# Core_Shield_Shield.net
KiCad netlist of a schematic drawn in EAGLE
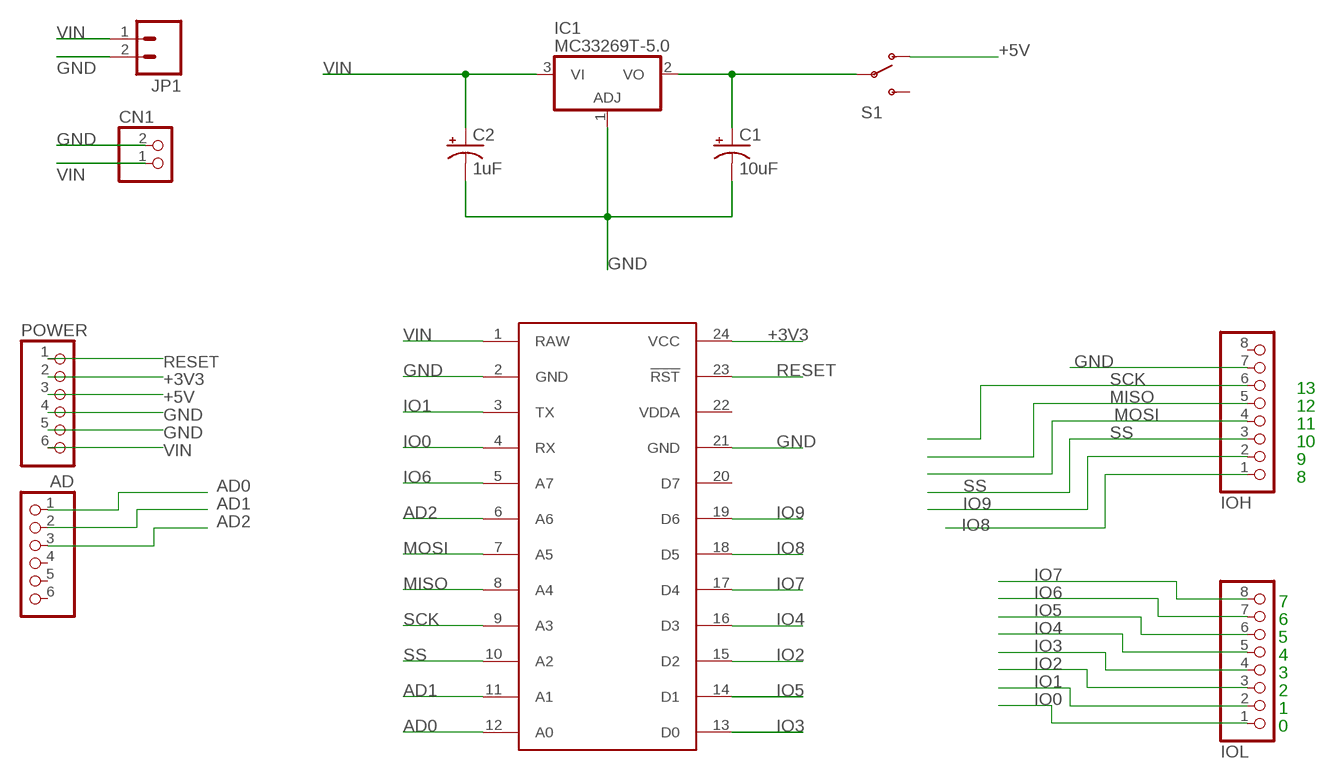
[diagram p0: schematic, sheet 1]

(export (version "E")
  (design (tool "Eeschema 10.0.6"))
  (components
    (comp (ref "AD")
      (value "PINHD-1X6")
      (footprint "eagle-import:1X06")
      (libsource (lib "eagle-import") (part "PINHD-1X6"))
    )
    (comp (ref "C1")
      (value "10uF")
      (footprint "eagle-import:CPOL-RADIAL-10UF-25V")
      (libsource (lib "eagle-import") (part "CAP_POLPTH2"))
    )
    (comp (ref "C2")
      (value "1uF")
      (footprint "eagle-import:CPOL-RADIAL-10UF-25V")
      (libsource (lib "eagle-import") (part "CAP_POLPTH2"))
    )
    (comp (ref "CN1")
      (value "JST_2PIN-THM")
      (footprint "eagle-import:JST-PH-2-THM")
      (libsource (lib "eagle-import") (part "JST_2PIN-THM"))
    )
    (comp (ref "IC1")
      (value "MC33269T-5.0")
      (footprint "eagle-import:TO220V")
      (libsource (lib "eagle-import") (part "MC33269?T-5.0"))
    )
    (comp (ref "IOH")
      (value "PINHD-1X8")
      (footprint "eagle-import:1X08")
      (libsource (lib "eagle-import") (part "PINHD-1X8"))
    )
    (comp (ref "IOL")
      (value "PINHD-1X8")
      (footprint "eagle-import:1X08")
      (libsource (lib "eagle-import") (part "PINHD-1X8"))
    )
    (comp (ref "JP1")
      (value "M02LOCK")
      (footprint "eagle-import:1X02_LOCK")
      (libsource (lib "eagle-import") (part "M02LOCK"))
    )
    (comp (ref "POWER")
      (value "PINHD-1X6")
      (footprint "eagle-import:1X06")
      (libsource (lib "eagle-import") (part "PINHD-1X6"))
    )
    (comp (ref "S1")
      (value "SWITCH-SPDTPTH")
      (footprint "eagle-import:SWITCH-SPDT")
      (libsource (lib "eagle-import") (part "SWITCH-SPDTPTH"))
    )
    (comp (ref "U$1")
      (value "SPARK_CORECORE")
      (footprint "eagle-import:SPARK_CORE")
      (libsource (lib "eagle-import") (part "SPARK_CORECORE"))
    )
  )
  (nets
    (net (code "1") (name "/+3V3") (class "Default")
      (node (ref "POWER") (pin "2") (pinfunction "2_2") (pintype "passive"))
      (node (ref "U$1") (pin "24") (pinfunction "VCC_24") (pintype "power_in"))
    )
    (net (code "2") (name "/+5V") (class "Default")
      (node (ref "POWER") (pin "3") (pinfunction "3_3") (pintype "passive"))
      (node (ref "S1") (pin "1") (pinfunction "O_1") (pintype "passive"))
    )
    (net (code "3") (name "/AD0") (class "Default")
      (node (ref "AD") (pin "1") (pinfunction "1_1") (pintype "passive"))
      (node (ref "U$1") (pin "12") (pinfunction "A0_12") (pintype "bidirectional"))
    )
    (net (code "4") (name "/AD1") (class "Default")
      (node (ref "AD") (pin "2") (pinfunction "2_2") (pintype "passive"))
      (node (ref "U$1") (pin "11") (pinfunction "A1_11") (pintype "bidirectional"))
    )
    (net (code "5") (name "/AD2") (class "Default")
      (node (ref "AD") (pin "3") (pinfunction "3_3") (pintype "passive"))
      (node (ref "U$1") (pin "6") (pinfunction "A6_6") (pintype "bidirectional"))
    )
    (net (code "6") (name "/GND") (class "Default")
      (node (ref "C1") (pin "2") (pinfunction "-_2") (pintype "passive"))
      (node (ref "C2") (pin "2") (pinfunction "-_2") (pintype "passive"))
      (node (ref "CN1") (pin "2") (pinfunction "1_2") (pintype "passive"))
      (node (ref "IC1") (pin "1") (pinfunction "ADJ_1") (pintype "input"))
      (node (ref "IOH") (pin "7") (pinfunction "7_7") (pintype "passive"))
      (node (ref "JP1") (pin "2") (pinfunction "2_2") (pintype "passive"))
      (node (ref "POWER") (pin "4") (pinfunction "4_4") (pintype "passive"))
      (node (ref "POWER") (pin "5") (pinfunction "5_5") (pintype "passive"))
      (node (ref "U$1") (pin "2") (pinfunction "GND_2") (pintype "power_in"))
      (node (ref "U$1") (pin "21") (pinfunction "GND_21") (pintype "power_in"))
    )
    (net (code "7") (name "/IO0") (class "Default")
      (node (ref "IOL") (pin "1") (pinfunction "1_1") (pintype "passive"))
      (node (ref "U$1") (pin "4") (pinfunction "RX_4") (pintype "bidirectional"))
    )
    (net (code "8") (name "/IO1") (class "Default")
      (node (ref "IOL") (pin "2") (pinfunction "2_2") (pintype "passive"))
      (node (ref "U$1") (pin "3") (pinfunction "TX_3") (pintype "bidirectional"))
    )
    (net (code "9") (name "/IO2") (class "Default")
      (node (ref "IOL") (pin "3") (pinfunction "3_3") (pintype "passive"))
      (node (ref "U$1") (pin "15") (pinfunction "D2_15") (pintype "bidirectional"))
    )
    (net (code "10") (name "/IO3") (class "Default")
      (node (ref "IOL") (pin "4") (pinfunction "4_4") (pintype "passive"))
      (node (ref "U$1") (pin "13") (pinfunction "D0_13") (pintype "bidirectional"))
    )
    (net (code "11") (name "/IO4") (class "Default")
      (node (ref "IOL") (pin "5") (pinfunction "5_5") (pintype "passive"))
      (node (ref "U$1") (pin "16") (pinfunction "D3_16") (pintype "bidirectional"))
    )
    (net (code "12") (name "/IO5") (class "Default")
      (node (ref "IOL") (pin "6") (pinfunction "6_6") (pintype "passive"))
      (node (ref "U$1") (pin "14") (pinfunction "D1_14") (pintype "bidirectional"))
    )
    (net (code "13") (name "/IO6") (class "Default")
      (node (ref "IOL") (pin "7") (pinfunction "7_7") (pintype "passive"))
      (node (ref "U$1") (pin "5") (pinfunction "A7_5") (pintype "bidirectional"))
    )
    (net (code "14") (name "/IO7") (class "Default")
      (node (ref "IOL") (pin "8") (pinfunction "8_8") (pintype "passive"))
      (node (ref "U$1") (pin "17") (pinfunction "D4_17") (pintype "bidirectional"))
    )
    (net (code "15") (name "/IO8") (class "Default")
      (node (ref "IOH") (pin "1") (pinfunction "1_1") (pintype "passive"))
      (node (ref "U$1") (pin "18") (pinfunction "D5_18") (pintype "bidirectional"))
    )
    (net (code "16") (name "/IO9") (class "Default")
      (node (ref "IOH") (pin "2") (pinfunction "2_2") (pintype "passive"))
      (node (ref "U$1") (pin "19") (pinfunction "D6_19") (pintype "bidirectional"))
    )
    (net (code "17") (name "/MISO") (class "Default")
      (node (ref "IOH") (pin "5") (pinfunction "5_5") (pintype "passive"))
      (node (ref "U$1") (pin "8") (pinfunction "A4_8") (pintype "bidirectional"))
    )
    (net (code "18") (name "/MOSI") (class "Default")
      (node (ref "IOH") (pin "4") (pinfunction "4_4") (pintype "passive"))
      (node (ref "U$1") (pin "7") (pinfunction "A5_7") (pintype "bidirectional"))
    )
    (net (code "19") (name "/RESET") (class "Default")
      (node (ref "POWER") (pin "1") (pinfunction "1_1") (pintype "passive"))
      (node (ref "U$1") (pin "23") (pinfunction "~{RST}_23") (pintype "bidirectional"))
    )
    (net (code "20") (name "/SCK") (class "Default")
      (node (ref "IOH") (pin "6") (pinfunction "6_6") (pintype "passive"))
      (node (ref "U$1") (pin "9") (pinfunction "A3_9") (pintype "bidirectional"))
    )
    (net (code "21") (name "/SS") (class "Default")
      (node (ref "IOH") (pin "3") (pinfunction "3_3") (pintype "passive"))
      (node (ref "U$1") (pin "10") (pinfunction "A2_10") (pintype "bidirectional"))
    )
    (net (code "22") (name "/VDDA") (class "Default")
      (node (ref "U$1") (pin "22") (pinfunction "VDDA_22") (pintype "power_in"))
    )
    (net (code "23") (name "/VIN") (class "Default")
      (node (ref "C2") (pin "1") (pinfunction "+_1") (pintype "passive"))
      (node (ref "CN1") (pin "1") (pinfunction "2_1") (pintype "passive"))
      (node (ref "IC1") (pin "3") (pinfunction "VI_3") (pintype "input"))
      (node (ref "JP1") (pin "1") (pinfunction "1_1") (pintype "passive"))
      (node (ref "POWER") (pin "6") (pinfunction "6_6") (pintype "passive"))
      (node (ref "U$1") (pin "1") (pinfunction "RAW_1") (pintype "power_in"))
    )
    (net (code "24") (name "Net-(C1-+)") (class "Default")
      (node (ref "C1") (pin "1") (pinfunction "+_1") (pintype "passive"))
      (node (ref "IC1") (pin "2") (pinfunction "VO_2") (pintype "passive"))
      (node (ref "S1") (pin "2") (pinfunction "P_2") (pintype "passive"))
    )
    (net (code "25") (name "unconnected-(AD-Pad4)") (class "Default")
      (node (ref "AD") (pin "4") (pinfunction "4_4") (pintype "passive"))
    )
    (net (code "26") (name "unconnected-(AD-Pad5)") (class "Default")
      (node (ref "AD") (pin "5") (pinfunction "5_5") (pintype "passive"))
    )
    (net (code "27") (name "unconnected-(AD-Pad6)") (class "Default")
      (node (ref "AD") (pin "6") (pinfunction "6_6") (pintype "passive"))
    )
    (net (code "28") (name "unconnected-(IOH-Pad8)") (class "Default")
      (node (ref "IOH") (pin "8") (pinfunction "8_8") (pintype "passive"))
    )
    (net (code "29") (name "unconnected-(S1-S-Pad3)") (class "Default")
      (node (ref "S1") (pin "3") (pinfunction "S_3") (pintype "passive"))
    )
    (net (code "30") (name "unconnected-(U$1-D7-Pad20)") (class "Default")
      (node (ref "U$1") (pin "20") (pinfunction "D7_20") (pintype "bidirectional"))
    )
  )
)
